# 32x_Ultimate_videoboard_7.net
KiCad netlist of a schematic drawn in EAGLE
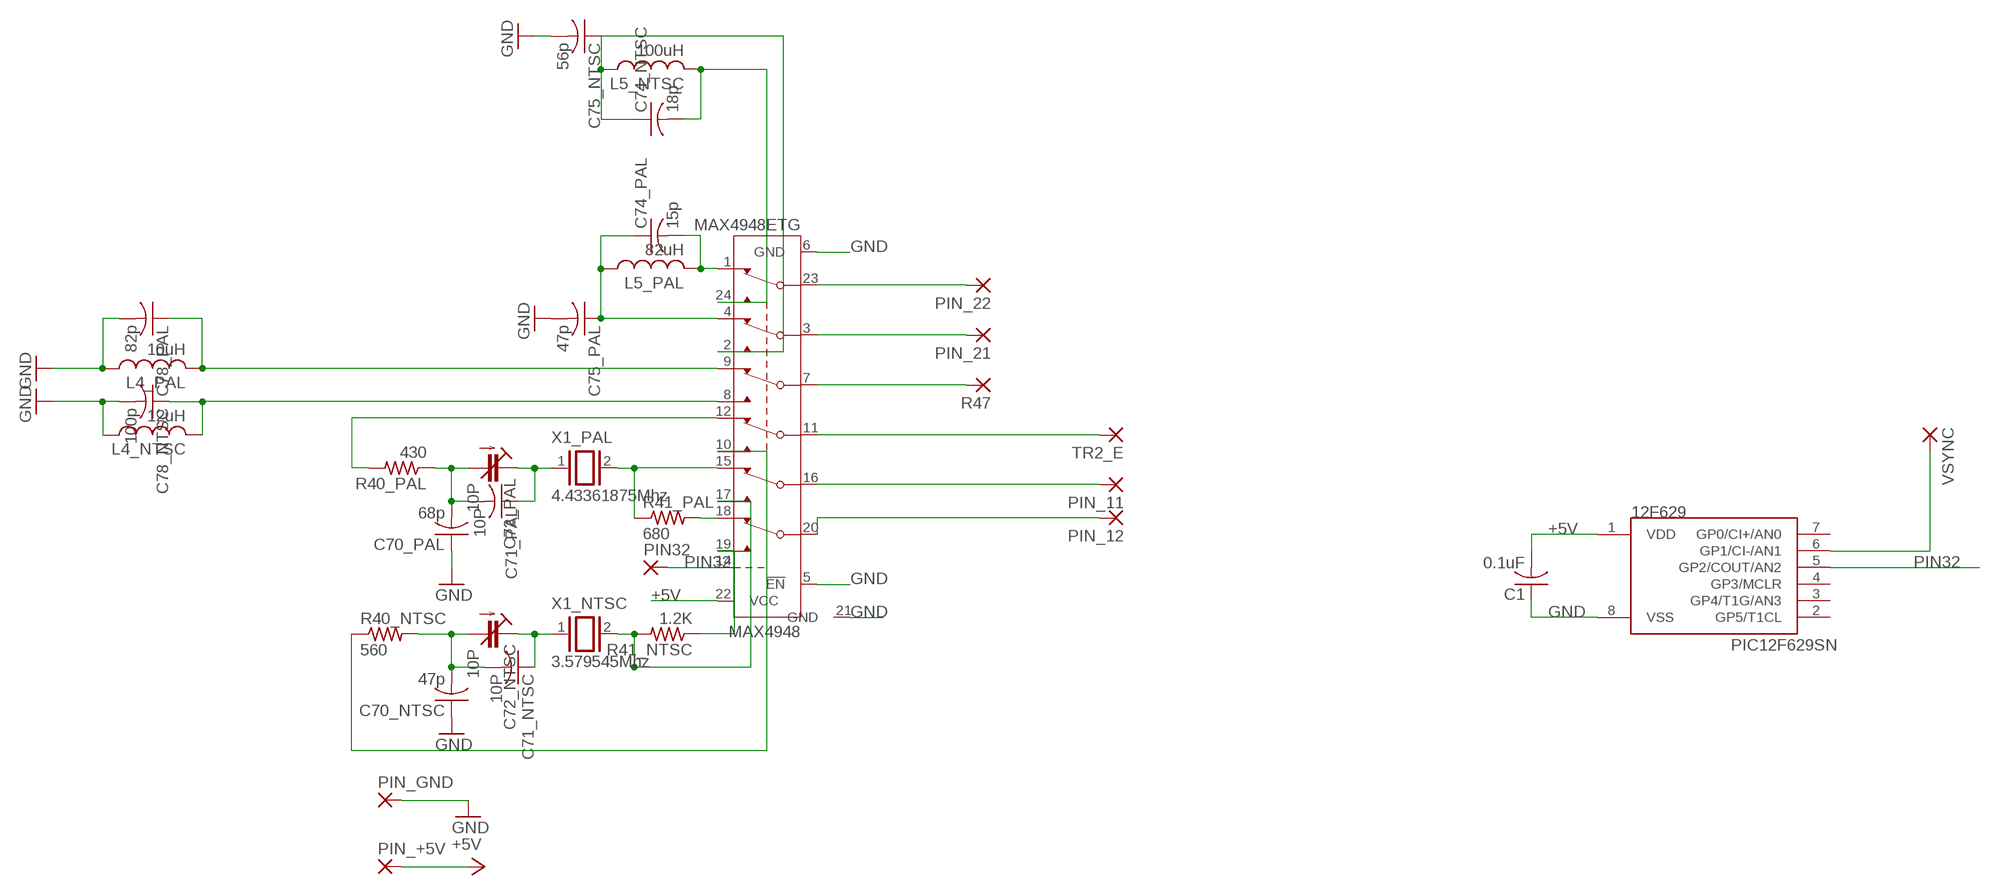
[diagram p0: schematic, sheet 1]

(export (version "E")
  (design (tool "Eeschema 10.0.6"))
  (components
    (comp (ref "12F629")
      (value "PIC12F629SN")
      (footprint "eagle-import:SO-08")
      (libsource (lib "eagle-import") (part "PIC12F6SN29"))
    )
    (comp (ref "C1")
      (value "0.1uF")
      (footprint "eagle-import:C0603")
      (libsource (lib "eagle-import") (part "C-USC0603"))
    )
    (comp (ref "C70_NTSC")
      (value "47p")
      (footprint "eagle-import:C0603")
      (libsource (lib "eagle-import") (part "C-USC0603"))
    )
    (comp (ref "C70_PAL")
      (value "68p")
      (footprint "eagle-import:C0603")
      (libsource (lib "eagle-import") (part "C-USC0603"))
    )
    (comp (ref "C71_NTSC")
      (value "10P")
      (footprint "eagle-import:C0603")
      (libsource (lib "eagle-import") (part "C-USC0603"))
    )
    (comp (ref "C71_PAL")
      (value "10P")
      (footprint "eagle-import:C0603")
      (libsource (lib "eagle-import") (part "C-USC0603"))
    )
    (comp (ref "C72_NTSC")
      (value "10P")
      (footprint "eagle-import:CTRIMTZBX4")
      (libsource (lib "eagle-import") (part "C-TRIMMTZBX4"))
    )
    (comp (ref "C72_PAL")
      (value "10P")
      (footprint "eagle-import:CTRIMTZBX4")
      (libsource (lib "eagle-import") (part "resistor_C-TRIMMTZBX4"))
    )
    (comp (ref "C74_NTSC")
      (value "18p")
      (footprint "eagle-import:C0603")
      (libsource (lib "eagle-import") (part "C-USC0603"))
    )
    (comp (ref "C74_PAL")
      (value "15p")
      (footprint "eagle-import:C0603")
      (libsource (lib "eagle-import") (part "C-USC0603"))
    )
    (comp (ref "C75_NTSC")
      (value "56p")
      (footprint "eagle-import:C0603")
      (libsource (lib "eagle-import") (part "C-USC0603"))
    )
    (comp (ref "C75_PAL")
      (value "47p")
      (footprint "eagle-import:C0603")
      (libsource (lib "eagle-import") (part "C-USC0603"))
    )
    (comp (ref "C78_NTSC")
      (value "100p")
      (footprint "eagle-import:C0603")
      (libsource (lib "eagle-import") (part "resistor_348_C-USC0603"))
    )
    (comp (ref "C78_PAL")
      (value "82p")
      (footprint "eagle-import:C0603")
      (libsource (lib "eagle-import") (part "C-USC0603"))
    )
    (comp (ref "L4_NTSC")
      (value "12uH")
      (footprint "eagle-import:L2012C")
      (libsource (lib "eagle-import") (part "L-USL2012C"))
    )
    (comp (ref "L4_PAL")
      (value "10uH")
      (footprint "eagle-import:L2012C")
      (libsource (lib "eagle-import") (part "L-USL2012C"))
    )
    (comp (ref "L5_NTSC")
      (value "100uH")
      (footprint "eagle-import:L2012C")
      (libsource (lib "eagle-import") (part "L-USL2012C"))
    )
    (comp (ref "L5_PAL")
      (value "82uH")
      (footprint "eagle-import:L2012C")
      (libsource (lib "eagle-import") (part "L-USL2012C"))
    )
    (comp (ref "MAX4948")
      (value "MAX4948ETG")
      (footprint "eagle-import:TQFN24-EP")
      (fields (field (name "MPN") "MAX4948ETG+"))
      (libsource (lib "eagle-import") (part "MAX4948ETG"))
    )
    (comp (ref "PIN32")
      (value "SMD2")
      (footprint "eagle-import:SMD1,27-2,54")
      (libsource (lib "eagle-import") (part "SMD2"))
    )
    (comp (ref "PIN_+5V")
      (value "SMD5")
      (footprint "eagle-import:SMD2,54-5,08")
      (libsource (lib "eagle-import") (part "SMD5"))
    )
    (comp (ref "PIN_11")
      (value "SMD2")
      (footprint "eagle-import:SMD1,27-2,54")
      (libsource (lib "eagle-import") (part "SMD2"))
    )
    (comp (ref "PIN_12")
      (value "SMD2")
      (footprint "eagle-import:SMD1,27-2,54")
      (libsource (lib "eagle-import") (part "SMD2"))
    )
    (comp (ref "PIN_21")
      (value "SMD2")
      (footprint "eagle-import:SMD1,27-2,54")
      (libsource (lib "eagle-import") (part "SMD2"))
    )
    (comp (ref "PIN_22")
      (value "SMD2")
      (footprint "eagle-import:SMD1,27-2,54")
      (libsource (lib "eagle-import") (part "SMD2"))
    )
    (comp (ref "PIN_GND")
      (value "SMD5")
      (footprint "eagle-import:SMD2,54-5,08")
      (libsource (lib "eagle-import") (part "SMD5"))
    )
    (comp (ref "R40_NTSC")
      (value "560")
      (footprint "eagle-import:R0603")
      (libsource (lib "eagle-import") (part "R-US_R0603"))
    )
    (comp (ref "R40_PAL")
      (value "430")
      (footprint "eagle-import:R0603")
      (libsource (lib "eagle-import") (part "resistor_348_R-US_R0603"))
    )
    (comp (ref "R41_NTSC")
      (value "1.2K")
      (footprint "eagle-import:R0603")
      (libsource (lib "eagle-import") (part "R-US_R0603"))
    )
    (comp (ref "R41_PAL")
      (value "680")
      (footprint "eagle-import:R0603")
      (libsource (lib "eagle-import") (part "R-US_R0603"))
    )
    (comp (ref "R47")
      (value "SMD2")
      (footprint "eagle-import:SMD1,27-2,54")
      (libsource (lib "eagle-import") (part "SMD2"))
    )
    (comp (ref "TR2_E")
      (value "SMD2")
      (footprint "eagle-import:SMD1,27-2,54")
      (libsource (lib "eagle-import") (part "SMD2"))
    )
    (comp (ref "VSYNC")
      (value "SMD2")
      (footprint "eagle-import:SMD1,27-2,54")
      (libsource (lib "eagle-import") (part "SMD2"))
    )
    (comp (ref "X1_NTSC")
      (value "3.579545Mhz")
      (footprint "eagle-import:QS")
      (libsource (lib "eagle-import") (part "XTAL/S"))
    )
    (comp (ref "X1_PAL")
      (value "4.43361875Mhz")
      (footprint "eagle-import:QS")
      (libsource (lib "eagle-import") (part "XTAL/S"))
    )
  )
  (nets
    (net (code "1") (name "+5V") (class "Default")
      (node (ref "12F629") (pin "1") (pinfunction "VDD_1") (pintype "power_in"))
      (node (ref "C1") (pin "2") (pinfunction "2_2") (pintype "passive"))
      (node (ref "MAX4948") (pin "22") (pinfunction "VCC_22") (pintype "power_in"))
      (node (ref "PIN_+5V") (pin "1") (pinfunction "P_1") (pintype "passive"))
    )
    (net (code "2") (name "/PIN32") (class "Default")
      (node (ref "12F629") (pin "5") (pinfunction "GP2/COUT/AN2_5") (pintype "bidirectional"))
      (node (ref "MAX4948") (pin "14") (pinfunction "CB_14") (pintype "input"))
      (node (ref "PIN32") (pin "1") (pinfunction "P_1") (pintype "passive"))
    )
    (net (code "3") (name "GND") (class "Default")
      (node (ref "12F629") (pin "8") (pinfunction "VSS_8") (pintype "power_in"))
      (node (ref "C1") (pin "1") (pinfunction "1_1") (pintype "passive"))
      (node (ref "C70_NTSC") (pin "1") (pinfunction "1_1") (pintype "passive"))
      (node (ref "C70_PAL") (pin "1") (pinfunction "1_1") (pintype "passive"))
      (node (ref "C75_NTSC") (pin "2") (pinfunction "2_2") (pintype "passive"))
      (node (ref "C75_PAL") (pin "2") (pinfunction "2_2") (pintype "passive"))
      (node (ref "C78_NTSC") (pin "2") (pinfunction "2_2") (pintype "passive"))
      (node (ref "C78_PAL") (pin "2") (pinfunction "2_2") (pintype "passive"))
      (node (ref "L4_NTSC") (pin "1") (pinfunction "1_1") (pintype "passive"))
      (node (ref "L4_PAL") (pin "1") (pinfunction "1_1") (pintype "passive"))
      (node (ref "MAX4948") (pin "21") (pinfunction "GND_21") (pintype "power_in"))
      (node (ref "MAX4948") (pin "5") (pinfunction "~{EN}_5") (pintype "input"))
      (node (ref "MAX4948") (pin "6") (pinfunction "GND_6") (pintype "power_in"))
      (node (ref "PIN_GND") (pin "1") (pinfunction "P_1") (pintype "passive"))
    )
    (net (code "4") (name "Net-(12F629-GP1{slash}CI-{slash}AN1)") (class "Default")
      (node (ref "12F629") (pin "6") (pinfunction "GP1/CI-/AN1_6") (pintype "bidirectional"))
      (node (ref "VSYNC") (pin "1") (pinfunction "P_1") (pintype "passive"))
    )
    (net (code "5") (name "Net-(C72_NTSC-A)") (class "Default")
      (node (ref "C70_NTSC") (pin "2") (pinfunction "2_2") (pintype "passive"))
      (node (ref "C71_NTSC") (pin "2") (pinfunction "2_2") (pintype "passive"))
      (node (ref "C72_NTSC") (pin "2") (pinfunction "A_2") (pintype "passive"))
      (node (ref "R40_NTSC") (pin "2") (pinfunction "2_2") (pintype "passive"))
    )
    (net (code "6") (name "Net-(C72_NTSC-E)") (class "Default")
      (node (ref "C71_NTSC") (pin "1") (pinfunction "1_1") (pintype "passive"))
      (node (ref "C72_NTSC") (pin "1") (pinfunction "E_1") (pintype "passive"))
      (node (ref "X1_NTSC") (pin "1") (pinfunction "1_1") (pintype "passive"))
    )
    (net (code "7") (name "Net-(C72_PAL-A)") (class "Default")
      (node (ref "C70_PAL") (pin "2") (pinfunction "2_2") (pintype "passive"))
      (node (ref "C71_PAL") (pin "2") (pinfunction "2_2") (pintype "passive"))
      (node (ref "C72_PAL") (pin "2") (pinfunction "A_2") (pintype "passive"))
      (node (ref "R40_PAL") (pin "1") (pinfunction "1_1") (pintype "passive"))
    )
    (net (code "8") (name "Net-(C72_PAL-E)") (class "Default")
      (node (ref "C71_PAL") (pin "1") (pinfunction "1_1") (pintype "passive"))
      (node (ref "C72_PAL") (pin "1") (pinfunction "E_1") (pintype "passive"))
      (node (ref "X1_PAL") (pin "1") (pinfunction "1_1") (pintype "passive"))
    )
    (net (code "9") (name "Net-(MAX4948B-COM1)") (class "Default")
      (node (ref "MAX4948") (pin "20") (pinfunction "COM1_20") (pintype "bidirectional"))
      (node (ref "PIN_12") (pin "1") (pinfunction "P_1") (pintype "passive"))
    )
    (net (code "10") (name "Net-(MAX4948B-COM2)") (class "Default")
      (node (ref "MAX4948") (pin "16") (pinfunction "COM2_16") (pintype "bidirectional"))
      (node (ref "PIN_11") (pin "1") (pinfunction "P_1") (pintype "passive"))
    )
    (net (code "11") (name "Net-(MAX4948B-COM3)") (class "Default")
      (node (ref "MAX4948") (pin "11") (pinfunction "COM3_11") (pintype "bidirectional"))
      (node (ref "TR2_E") (pin "1") (pinfunction "P_1") (pintype "passive"))
    )
    (net (code "12") (name "Net-(MAX4948B-COM4)") (class "Default")
      (node (ref "MAX4948") (pin "7") (pinfunction "COM4_7") (pintype "bidirectional"))
      (node (ref "R47") (pin "1") (pinfunction "P_1") (pintype "passive"))
    )
    (net (code "13") (name "Net-(MAX4948B-COM5)") (class "Default")
      (node (ref "MAX4948") (pin "3") (pinfunction "COM5_3") (pintype "bidirectional"))
      (node (ref "PIN_21") (pin "1") (pinfunction "P_1") (pintype "passive"))
    )
    (net (code "14") (name "Net-(MAX4948B-COM6)") (class "Default")
      (node (ref "MAX4948") (pin "23") (pinfunction "COM6_23") (pintype "bidirectional"))
      (node (ref "PIN_22") (pin "1") (pinfunction "P_1") (pintype "passive"))
    )
    (net (code "15") (name "Net-(MAX4948B-NC1)") (class "Default")
      (node (ref "MAX4948") (pin "18") (pinfunction "NC1_18") (pintype "bidirectional"))
      (node (ref "R41_PAL") (pin "2") (pinfunction "2_2") (pintype "passive"))
    )
    (net (code "16") (name "Net-(MAX4948B-NC2)") (class "Default")
      (node (ref "MAX4948") (pin "15") (pinfunction "NC2_15") (pintype "bidirectional"))
      (node (ref "R41_PAL") (pin "1") (pinfunction "1_1") (pintype "passive"))
      (node (ref "X1_PAL") (pin "2") (pinfunction "2_2") (pintype "passive"))
    )
    (net (code "17") (name "Net-(MAX4948B-NC3)") (class "Default")
      (node (ref "MAX4948") (pin "12") (pinfunction "NC3_12") (pintype "bidirectional"))
      (node (ref "R40_PAL") (pin "2") (pinfunction "2_2") (pintype "passive"))
    )
    (net (code "18") (name "Net-(MAX4948B-NC4)") (class "Default")
      (node (ref "C78_PAL") (pin "1") (pinfunction "1_1") (pintype "passive"))
      (node (ref "L4_PAL") (pin "2") (pinfunction "2_2") (pintype "passive"))
      (node (ref "MAX4948") (pin "9") (pinfunction "NC4_9") (pintype "bidirectional"))
    )
    (net (code "19") (name "Net-(MAX4948B-NC5)") (class "Default")
      (node (ref "C74_PAL") (pin "1") (pinfunction "1_1") (pintype "passive"))
      (node (ref "C75_PAL") (pin "1") (pinfunction "1_1") (pintype "passive"))
      (node (ref "L5_PAL") (pin "1") (pinfunction "1_1") (pintype "passive"))
      (node (ref "MAX4948") (pin "4") (pinfunction "NC5_4") (pintype "bidirectional"))
    )
    (net (code "20") (name "Net-(MAX4948B-NC6)") (class "Default")
      (node (ref "C74_PAL") (pin "2") (pinfunction "2_2") (pintype "passive"))
      (node (ref "L5_PAL") (pin "2") (pinfunction "2_2") (pintype "passive"))
      (node (ref "MAX4948") (pin "1") (pinfunction "NC6_1") (pintype "bidirectional"))
    )
    (net (code "21") (name "Net-(MAX4948B-NO1)") (class "Default")
      (node (ref "MAX4948") (pin "19") (pinfunction "NO1_19") (pintype "bidirectional"))
      (node (ref "R41_NTSC") (pin "1") (pinfunction "1_1") (pintype "passive"))
    )
    (net (code "22") (name "Net-(MAX4948B-NO2)") (class "Default")
      (node (ref "MAX4948") (pin "17") (pinfunction "NO2_17") (pintype "bidirectional"))
      (node (ref "R41_NTSC") (pin "2") (pinfunction "2_2") (pintype "passive"))
      (node (ref "X1_NTSC") (pin "2") (pinfunction "2_2") (pintype "passive"))
    )
    (net (code "23") (name "Net-(MAX4948B-NO3)") (class "Default")
      (node (ref "MAX4948") (pin "10") (pinfunction "NO3_10") (pintype "bidirectional"))
      (node (ref "R40_NTSC") (pin "1") (pinfunction "1_1") (pintype "passive"))
    )
    (net (code "24") (name "Net-(MAX4948B-NO4)") (class "Default")
      (node (ref "C78_NTSC") (pin "1") (pinfunction "1_1") (pintype "passive"))
      (node (ref "L4_NTSC") (pin "2") (pinfunction "2_2") (pintype "passive"))
      (node (ref "MAX4948") (pin "8") (pinfunction "NO4_8") (pintype "bidirectional"))
    )
    (net (code "25") (name "Net-(MAX4948B-NO5)") (class "Default")
      (node (ref "C74_NTSC") (pin "1") (pinfunction "1_1") (pintype "passive"))
      (node (ref "C75_NTSC") (pin "1") (pinfunction "1_1") (pintype "passive"))
      (node (ref "L5_NTSC") (pin "1") (pinfunction "1_1") (pintype "passive"))
      (node (ref "MAX4948") (pin "2") (pinfunction "NO5_2") (pintype "bidirectional"))
    )
    (net (code "26") (name "Net-(MAX4948B-NO6)") (class "Default")
      (node (ref "C74_NTSC") (pin "2") (pinfunction "2_2") (pintype "passive"))
      (node (ref "L5_NTSC") (pin "2") (pinfunction "2_2") (pintype "passive"))
      (node (ref "MAX4948") (pin "24") (pinfunction "NO6_24") (pintype "bidirectional"))
    )
    (net (code "27") (name "unconnected-(12F629-GP0{slash}CI+{slash}AN0-Pad7)") (class "Default")
      (node (ref "12F629") (pin "7") (pinfunction "GP0/CI+/AN0_7") (pintype "bidirectional"))
    )
    (net (code "28") (name "unconnected-(12F629-GP3{slash}MCLR-Pad4)") (class "Default")
      (node (ref "12F629") (pin "4") (pinfunction "GP3/MCLR_4") (pintype "input"))
    )
    (net (code "29") (name "unconnected-(12F629-GP4{slash}T1G{slash}AN3-Pad3)") (class "Default")
      (node (ref "12F629") (pin "3") (pinfunction "GP4/T1G/AN3_3") (pintype "bidirectional"))
    )
    (net (code "30") (name "unconnected-(12F629-GP5{slash}T1CL-Pad2)") (class "Default")
      (node (ref "12F629") (pin "2") (pinfunction "GP5/T1CL_2") (pintype "bidirectional"))
    )
  )
)
